# gnat-1.net
KiCad netlist of a schematic drawn in EAGLE
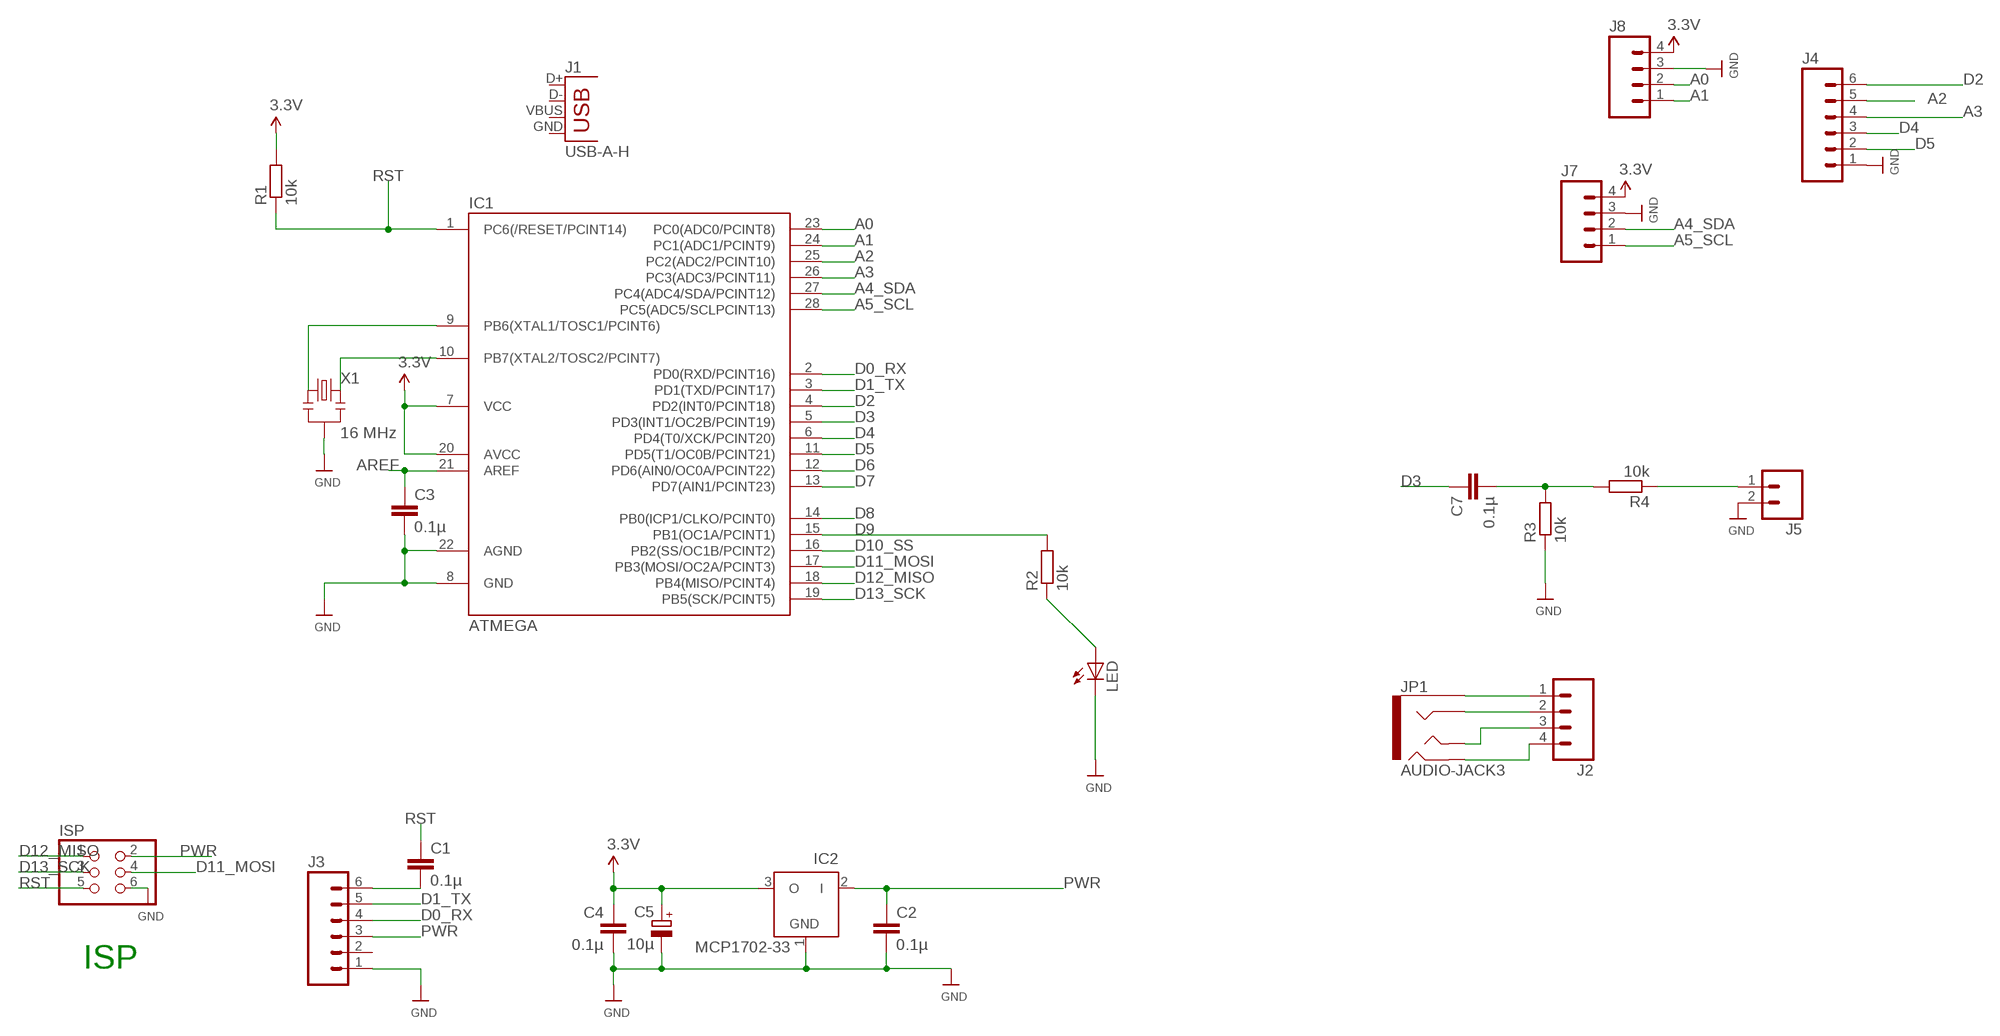
[diagram p0: schematic, sheet 1]

(export (version "E")
  (design (tool "Eeschema 10.0.6"))
  (components
    (comp (ref "C1")
      (value "0.1µ")
      (footprint "eagle-import:C025-024X044")
      (libsource (lib "eagle-import") (part "C-EU025-024X044"))
    )
    (comp (ref "C2")
      (value "0.1µ")
      (footprint "eagle-import:C025-024X044")
      (libsource (lib "eagle-import") (part "C-EU025-024X044"))
    )
    (comp (ref "C3")
      (value "0.1µ")
      (footprint "eagle-import:C025-024X044")
      (libsource (lib "eagle-import") (part "C-EU025-024X044"))
    )
    (comp (ref "C4")
      (value "0.1µ")
      (footprint "eagle-import:C025-024X044")
      (libsource (lib "eagle-import") (part "C-EU025-024X044"))
    )
    (comp (ref "C5")
      (value "10µ")
      (footprint "eagle-import:E1,8-4")
      (libsource (lib "eagle-import") (part "CPOL-EUE1.8-4"))
    )
    (comp (ref "C7")
      (value "0.1µ")
      (footprint "eagle-import:C025-024X044")
      (libsource (lib "eagle-import") (part "C-EU025-024X044"))
    )
    (comp (ref "IC1")
      (value "ATMEGA")
      (footprint "eagle-import:DIL28-3")
      (libsource (lib "eagle-import") (part "ATMEGA48/88/168-PU"))
    )
    (comp (ref "IC2")
      (value "MCP1702-33")
      (footprint "eagle-import:TO92")
      (libsource (lib "eagle-import") (part "MCP1702Z"))
    )
    (comp (ref "ISP")
      (value "PINHD-2X3")
      (footprint "eagle-import:2X03")
      (libsource (lib "eagle-import") (part "PINHD-2X3"))
    )
    (comp (ref "J1")
      (value "USB-A-H")
      (footprint "eagle-import:USB-A-H")
      (libsource (lib "eagle-import") (part "USB-A-H"))
    )
    (comp (ref "J2")
      (value "M04PTH")
      (footprint "eagle-import:1X04")
      (libsource (lib "eagle-import") (part "M04PTH"))
    )
    (comp (ref "J3")
      (value "M06SILK_FEMALE_PTH")
      (footprint "eagle-import:1X06")
      (libsource (lib "eagle-import") (part "M06SILK_FEMALE_PTH"))
    )
    (comp (ref "J4")
      (value "M06SILK_FEMALE_PTH")
      (footprint "eagle-import:1X06")
      (libsource (lib "eagle-import") (part "M06SILK_FEMALE_PTH"))
    )
    (comp (ref "J5")
      (value "M02PTH")
      (footprint "eagle-import:1X02")
      (libsource (lib "eagle-import") (part "M02PTH"))
    )
    (comp (ref "J7")
      (value "M04SCREW")
      (footprint "eagle-import:SCREWTERMINAL-3.5MM-4")
      (libsource (lib "eagle-import") (part "M04SCREW"))
    )
    (comp (ref "J8")
      (value "M04SCREW")
      (footprint "eagle-import:SCREWTERMINAL-3.5MM-4")
      (libsource (lib "eagle-import") (part "M04SCREW"))
    )
    (comp (ref "JP1")
      (value "AUDIO-JACK3")
      (footprint "eagle-import:AUDIO-JACK-TRRS-SMD")
      (libsource (lib "eagle-import") (part "AUDIO-JACK3"))
    )
    (comp (ref "LED")
      (value "LED3MM")
      (footprint "eagle-import:LED3MM")
      (libsource (lib "eagle-import") (part "LED3MM"))
    )
    (comp (ref "R1")
      (value "10k")
      (footprint "eagle-import:0204_7")
      (libsource (lib "eagle-import") (part "R-EU_0204/7"))
    )
    (comp (ref "R2")
      (value "10k")
      (footprint "eagle-import:0204_7")
      (libsource (lib "eagle-import") (part "R-EU_0204/7"))
    )
    (comp (ref "R3")
      (value "10k")
      (footprint "eagle-import:0204_7")
      (libsource (lib "eagle-import") (part "R-EU_0204/7"))
    )
    (comp (ref "R4")
      (value "10k")
      (footprint "eagle-import:0204_7")
      (libsource (lib "eagle-import") (part "R-EU_0204/7"))
    )
    (comp (ref "X1")
      (value "16 MHz")
      (footprint "eagle-import:RESONATOR-PTH")
      (libsource (lib "eagle-import") (part "RESONATORPTH"))
    )
  )
  (nets
    (net (code "1") (name "/A0") (class "Default")
      (node (ref "IC1") (pin "23") (pinfunction "PC0(ADC0/PCINT8)_23") (pintype "bidirectional"))
      (node (ref "J8") (pin "2") (pinfunction "2_2") (pintype "passive"))
    )
    (net (code "2") (name "/A1") (class "Default")
      (node (ref "IC1") (pin "24") (pinfunction "PC1(ADC1/PCINT9)_24") (pintype "bidirectional"))
      (node (ref "J8") (pin "1") (pinfunction "1_1") (pintype "passive"))
    )
    (net (code "3") (name "/A2") (class "Default")
      (node (ref "IC1") (pin "25") (pinfunction "PC2(ADC2/PCINT10)_25") (pintype "bidirectional"))
      (node (ref "J4") (pin "5") (pinfunction "5_5") (pintype "passive"))
    )
    (net (code "4") (name "/A3") (class "Default")
      (node (ref "IC1") (pin "26") (pinfunction "PC3(ADC3/PCINT11)_26") (pintype "bidirectional"))
      (node (ref "J4") (pin "4") (pinfunction "4_4") (pintype "passive"))
    )
    (net (code "5") (name "/A4_SDA") (class "Default")
      (node (ref "IC1") (pin "27") (pinfunction "PC4(ADC4/SDA/PCINT12)_27") (pintype "bidirectional"))
      (node (ref "J7") (pin "2") (pinfunction "2_2") (pintype "passive"))
    )
    (net (code "6") (name "/A5_SCL") (class "Default")
      (node (ref "IC1") (pin "28") (pinfunction "PC5(ADC5/SCLPCINT13)_28") (pintype "bidirectional"))
      (node (ref "J7") (pin "1") (pinfunction "1_1") (pintype "passive"))
    )
    (net (code "7") (name "/AREF") (class "Default")
      (node (ref "C3") (pin "1") (pinfunction "1_1") (pintype "passive"))
      (node (ref "IC1") (pin "21") (pinfunction "AREF_21") (pintype "passive"))
    )
    (net (code "8") (name "/D0_RX") (class "Default")
      (node (ref "IC1") (pin "2") (pinfunction "PD0(RXD/PCINT16)_2") (pintype "bidirectional"))
      (node (ref "J3") (pin "4") (pinfunction "4_4") (pintype "passive"))
    )
    (net (code "9") (name "/D1_TX") (class "Default")
      (node (ref "IC1") (pin "3") (pinfunction "PD1(TXD/PCINT17)_3") (pintype "bidirectional"))
      (node (ref "J3") (pin "5") (pinfunction "5_5") (pintype "passive"))
    )
    (net (code "10") (name "/D2") (class "Default")
      (node (ref "IC1") (pin "4") (pinfunction "PD2(INT0/PCINT18)_4") (pintype "bidirectional"))
      (node (ref "J4") (pin "6") (pinfunction "6_6") (pintype "passive"))
    )
    (net (code "11") (name "/D3") (class "Default")
      (node (ref "C7") (pin "1") (pinfunction "1_1") (pintype "passive"))
      (node (ref "IC1") (pin "5") (pinfunction "PD3(INT1/OC2B/PCINT19)_5") (pintype "bidirectional"))
    )
    (net (code "12") (name "/D4") (class "Default")
      (node (ref "IC1") (pin "6") (pinfunction "PD4(T0/XCK/PCINT20)_6") (pintype "bidirectional"))
      (node (ref "J4") (pin "3") (pinfunction "3_3") (pintype "passive"))
    )
    (net (code "13") (name "/D5") (class "Default")
      (node (ref "IC1") (pin "11") (pinfunction "PD5(T1/OC0B/PCINT21)_11") (pintype "bidirectional"))
      (node (ref "J4") (pin "2") (pinfunction "2_2") (pintype "passive"))
    )
    (net (code "14") (name "/D6") (class "Default")
      (node (ref "IC1") (pin "12") (pinfunction "PD6(AIN0/OC0A/PCINT22)_12") (pintype "bidirectional"))
    )
    (net (code "15") (name "/D7") (class "Default")
      (node (ref "IC1") (pin "13") (pinfunction "PD7(AIN1/PCINT23)_13") (pintype "bidirectional"))
    )
    (net (code "16") (name "/D8") (class "Default")
      (node (ref "IC1") (pin "14") (pinfunction "PB0(ICP1/CLKO/PCINT0)_14") (pintype "bidirectional"))
    )
    (net (code "17") (name "/D9") (class "Default")
      (node (ref "IC1") (pin "15") (pinfunction "PB1(OC1A/PCINT1)_15") (pintype "bidirectional"))
      (node (ref "R2") (pin "2") (pinfunction "2_2") (pintype "passive"))
    )
    (net (code "18") (name "/D10_SS") (class "Default")
      (node (ref "IC1") (pin "16") (pinfunction "PB2(SS/OC1B/PCINT2)_16") (pintype "bidirectional"))
    )
    (net (code "19") (name "/D11_MOSI") (class "Default")
      (node (ref "IC1") (pin "17") (pinfunction "PB3(MOSI/OC2A/PCINT3)_17") (pintype "bidirectional"))
      (node (ref "ISP") (pin "4") (pinfunction "4_4") (pintype "passive"))
    )
    (net (code "20") (name "/D12_MISO") (class "Default")
      (node (ref "IC1") (pin "18") (pinfunction "PB4(MISO/PCINT4)_18") (pintype "bidirectional"))
      (node (ref "ISP") (pin "1") (pinfunction "1_1") (pintype "passive"))
    )
    (net (code "21") (name "/D13_SCK") (class "Default")
      (node (ref "IC1") (pin "19") (pinfunction "PB5(SCK/PCINT5)_19") (pintype "bidirectional"))
      (node (ref "ISP") (pin "3") (pinfunction "3_3") (pintype "passive"))
    )
    (net (code "22") (name "/PWR") (class "Default")
      (node (ref "C2") (pin "1") (pinfunction "1_1") (pintype "passive"))
      (node (ref "IC2") (pin "2") (pinfunction "I_2") (pintype "input"))
      (node (ref "ISP") (pin "2") (pinfunction "2_2") (pintype "passive"))
      (node (ref "J3") (pin "3") (pinfunction "3_3") (pintype "passive"))
    )
    (net (code "23") (name "/RST") (class "Default")
      (node (ref "C1") (pin "1") (pinfunction "1_1") (pintype "passive"))
      (node (ref "IC1") (pin "1") (pinfunction "PC6(/RESET/PCINT14)_1") (pintype "bidirectional"))
      (node (ref "ISP") (pin "5") (pinfunction "5_5") (pintype "passive"))
      (node (ref "R1") (pin "1") (pinfunction "1_1") (pintype "passive"))
    )
    (net (code "24") (name "3.3V") (class "Default")
      (node (ref "C4") (pin "1") (pinfunction "1_1") (pintype "passive"))
      (node (ref "C5") (pin "+") (pinfunction "+_+") (pintype "passive"))
      (node (ref "IC1") (pin "20") (pinfunction "AVCC_20") (pintype "passive"))
      (node (ref "IC1") (pin "7") (pinfunction "VCC_7") (pintype "power_in"))
      (node (ref "IC2") (pin "3") (pinfunction "O_3") (pintype "input"))
      (node (ref "J7") (pin "4") (pinfunction "4_4") (pintype "passive"))
      (node (ref "J8") (pin "4") (pinfunction "4_4") (pintype "passive"))
      (node (ref "R1") (pin "2") (pinfunction "2_2") (pintype "passive"))
    )
    (net (code "25") (name "GND") (class "Default")
      (node (ref "C2") (pin "2") (pinfunction "2_2") (pintype "passive"))
      (node (ref "C3") (pin "2") (pinfunction "2_2") (pintype "passive"))
      (node (ref "C4") (pin "2") (pinfunction "2_2") (pintype "passive"))
      (node (ref "C5") (pin "-") (pinfunction "-_-") (pintype "passive"))
      (node (ref "IC1") (pin "22") (pinfunction "AGND_22") (pintype "power_in"))
      (node (ref "IC1") (pin "8") (pinfunction "GND_8") (pintype "power_in"))
      (node (ref "IC2") (pin "1") (pinfunction "GND_1") (pintype "power_in"))
      (node (ref "ISP") (pin "6") (pinfunction "6_6") (pintype "passive"))
      (node (ref "J3") (pin "1") (pinfunction "1_1") (pintype "passive"))
      (node (ref "J4") (pin "1") (pinfunction "1_1") (pintype "passive"))
      (node (ref "J5") (pin "2") (pinfunction "2_2") (pintype "passive"))
      (node (ref "J7") (pin "3") (pinfunction "3_3") (pintype "passive"))
      (node (ref "J8") (pin "3") (pinfunction "3_3") (pintype "passive"))
      (node (ref "LED") (pin "K") (pinfunction "C_K") (pintype "passive"))
      (node (ref "R3") (pin "1") (pinfunction "1_1") (pintype "passive"))
      (node (ref "X1") (pin "2") (pinfunction "2_2") (pintype "passive"))
    )
    (net (code "26") (name "Net-(C1-Pad2)") (class "Default")
      (node (ref "C1") (pin "2") (pinfunction "2_2") (pintype "passive"))
      (node (ref "J3") (pin "6") (pinfunction "6_6") (pintype "passive"))
    )
    (net (code "27") (name "Net-(C7-Pad2)") (class "Default")
      (node (ref "C7") (pin "2") (pinfunction "2_2") (pintype "passive"))
      (node (ref "R3") (pin "2") (pinfunction "2_2") (pintype "passive"))
      (node (ref "R4") (pin "2") (pinfunction "2_2") (pintype "passive"))
    )
    (net (code "28") (name "Net-(IC1-PB6(XTAL1{slash}TOSC1{slash}PCINT6))") (class "Default")
      (node (ref "IC1") (pin "9") (pinfunction "PB6(XTAL1/TOSC1/PCINT6)_9") (pintype "bidirectional"))
      (node (ref "X1") (pin "1") (pinfunction "1_1") (pintype "passive"))
    )
    (net (code "29") (name "Net-(IC1-PB7(XTAL2{slash}TOSC2{slash}PCINT7))") (class "Default")
      (node (ref "IC1") (pin "10") (pinfunction "PB7(XTAL2/TOSC2/PCINT7)_10") (pintype "bidirectional"))
      (node (ref "X1") (pin "3") (pinfunction "3_3") (pintype "passive"))
    )
    (net (code "30") (name "Net-(J2-Pad1)") (class "Default")
      (node (ref "J2") (pin "1") (pinfunction "1_1") (pintype "passive"))
      (node (ref "JP1") (pin "EARTH") (pinfunction "EARTH_EARTH") (pintype "bidirectional"))
    )
    (net (code "31") (name "Net-(J2-Pad2)") (class "Default")
      (node (ref "J2") (pin "2") (pinfunction "2_2") (pintype "passive"))
      (node (ref "JP1") (pin "RING1") (pinfunction "RING1_RING1") (pintype "bidirectional"))
    )
    (net (code "32") (name "Net-(J2-Pad3)") (class "Default")
      (node (ref "J2") (pin "3") (pinfunction "3_3") (pintype "passive"))
      (node (ref "JP1") (pin "TIP") (pinfunction "TIP_TIP") (pintype "bidirectional"))
    )
    (net (code "33") (name "Net-(J2-Pad4)") (class "Default")
      (node (ref "J2") (pin "4") (pinfunction "4_4") (pintype "passive"))
      (node (ref "JP1") (pin "RING2") (pinfunction "RING2_RING2") (pintype "bidirectional"))
    )
    (net (code "34") (name "Net-(J5-Pad1)") (class "Default")
      (node (ref "J5") (pin "1") (pinfunction "1_1") (pintype "passive"))
      (node (ref "R4") (pin "1") (pinfunction "1_1") (pintype "passive"))
    )
    (net (code "35") (name "Net-(LED-PadA)") (class "Default")
      (node (ref "LED") (pin "A") (pinfunction "A_A") (pintype "passive"))
      (node (ref "R2") (pin "1") (pinfunction "1_1") (pintype "passive"))
    )
    (net (code "36") (name "unconnected-(J1-PadD+)") (class "Default")
      (node (ref "J1") (pin "D+") (pinfunction "D+_D+") (pintype "bidirectional"))
    )
    (net (code "37") (name "unconnected-(J1-PadD-)") (class "Default")
      (node (ref "J1") (pin "D-") (pinfunction "D-_D-") (pintype "bidirectional"))
    )
    (net (code "38") (name "unconnected-(J1-PadGND)") (class "Default")
      (node (ref "J1") (pin "GND") (pinfunction "GND_GND") (pintype "bidirectional"))
    )
    (net (code "39") (name "unconnected-(J1-PadVBUS)") (class "Default")
      (node (ref "J1") (pin "VBUS") (pinfunction "VBUS_VBUS") (pintype "bidirectional"))
    )
    (net (code "40") (name "unconnected-(J3-Pad2)") (class "Default")
      (node (ref "J3") (pin "2") (pinfunction "2_2") (pintype "passive"))
    )
  )
)
